# TTGO_shield_revG.net
KiCad netlist of a schematic drawn in EAGLE
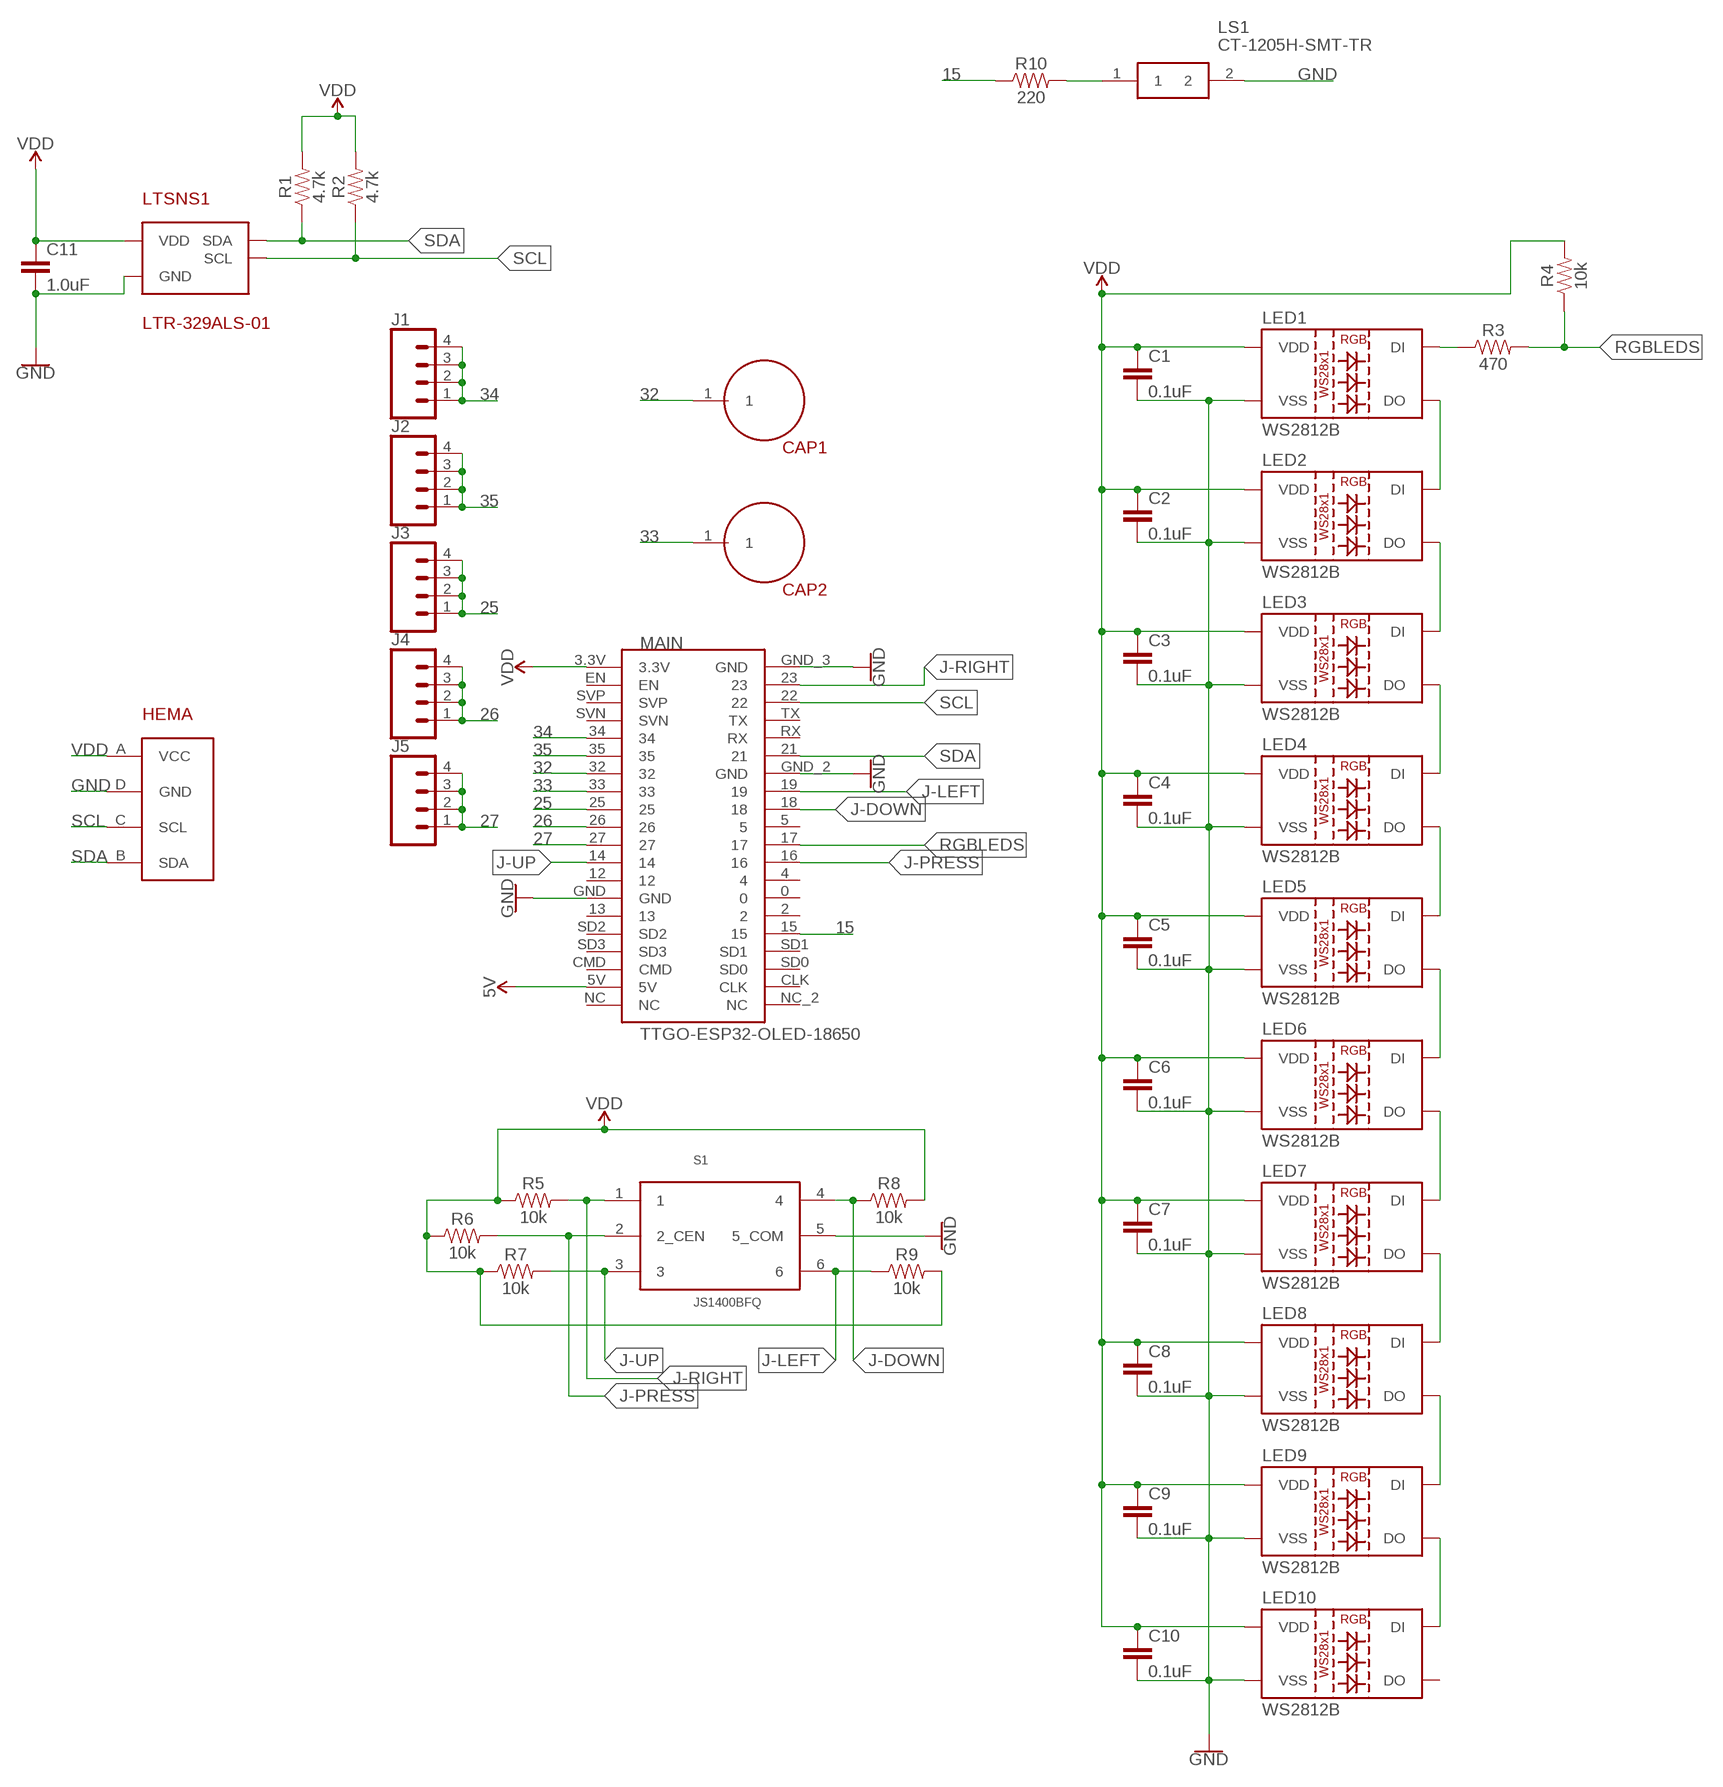
[diagram p0: schematic, sheet 1]

(export (version "E")
  (design (tool "Eeschema 10.0.6"))
  (components
    (comp (ref "C1")
      (value "0.1uF")
      (footprint "eagle-import:0603")
      (libsource (lib "eagle-import") (part "0.1UF-0603-25V-5%"))
    )
    (comp (ref "C2")
      (value "0.1uF")
      (footprint "eagle-import:0603")
      (libsource (lib "eagle-import") (part "0.1UF-0603-25V-5%"))
    )
    (comp (ref "C3")
      (value "0.1uF")
      (footprint "eagle-import:0603")
      (libsource (lib "eagle-import") (part "0.1UF-0603-25V-5%"))
    )
    (comp (ref "C4")
      (value "0.1uF")
      (footprint "eagle-import:0603")
      (libsource (lib "eagle-import") (part "0.1UF-0603-25V-5%"))
    )
    (comp (ref "C5")
      (value "0.1uF")
      (footprint "eagle-import:0603")
      (libsource (lib "eagle-import") (part "0.1UF-0603-25V-5%"))
    )
    (comp (ref "C6")
      (value "0.1uF")
      (footprint "eagle-import:0603")
      (libsource (lib "eagle-import") (part "0.1UF-0603-25V-5%"))
    )
    (comp (ref "C7")
      (value "0.1uF")
      (footprint "eagle-import:0603")
      (libsource (lib "eagle-import") (part "0.1UF-0603-25V-5%"))
    )
    (comp (ref "C8")
      (value "0.1uF")
      (footprint "eagle-import:0603")
      (libsource (lib "eagle-import") (part "0.1UF-0603-25V-5%"))
    )
    (comp (ref "C9")
      (value "0.1uF")
      (footprint "eagle-import:0603")
      (libsource (lib "eagle-import") (part "0.1UF-0603-25V-5%"))
    )
    (comp (ref "C10")
      (value "0.1uF")
      (footprint "eagle-import:0603")
      (libsource (lib "eagle-import") (part "0.1UF-0603-25V-5%"))
    )
    (comp (ref "C11")
      (value "1.0uF")
      (footprint "eagle-import:0805")
      (libsource (lib "eagle-import") (part "1.0UF-0805-25V-10%"))
    )
    (comp (ref "CAP1")
      (value "CAPSENSE_BUTTON")
      (footprint "eagle-import:CAPSENSE_BUTTON")
      (libsource (lib "eagle-import") (part "CAPSENSE_BUTTON"))
    )
    (comp (ref "CAP2")
      (value "CAPSENSE_BUTTON")
      (footprint "eagle-import:CAPSENSE_BUTTON")
      (libsource (lib "eagle-import") (part "CAPSENSE_BUTTON"))
    )
    (comp (ref "J1")
      (value "CONN_04LONGPADS")
      (footprint "eagle-import:1X04_LONGPADS")
      (libsource (lib "eagle-import") (part "CONN_04LONGPADS"))
    )
    (comp (ref "J2")
      (value "CONN_04LONGPADS")
      (footprint "eagle-import:1X04_LONGPADS")
      (libsource (lib "eagle-import") (part "CONN_04LONGPADS"))
    )
    (comp (ref "J3")
      (value "CONN_04LONGPADS")
      (footprint "eagle-import:1X04_LONGPADS")
      (libsource (lib "eagle-import") (part "CONN_04LONGPADS"))
    )
    (comp (ref "J4")
      (value "CONN_04LONGPADS")
      (footprint "eagle-import:1X04_LONGPADS")
      (libsource (lib "eagle-import") (part "CONN_04LONGPADS"))
    )
    (comp (ref "J5")
      (value "CONN_04LONGPADS")
      (footprint "eagle-import:1X04_LONGPADS")
      (libsource (lib "eagle-import") (part "CONN_04LONGPADS"))
    )
    (comp (ref "LED1")
      (value "WS2812B")
      (footprint "eagle-import:WS2812B")
      (libsource (lib "eagle-import") (part "WS2812B"))
    )
    (comp (ref "LED2")
      (value "WS2812B")
      (footprint "eagle-import:WS2812B")
      (libsource (lib "eagle-import") (part "WS2812B"))
    )
    (comp (ref "LED3")
      (value "WS2812B")
      (footprint "eagle-import:WS2812B")
      (libsource (lib "eagle-import") (part "WS2812B"))
    )
    (comp (ref "LED4")
      (value "WS2812B")
      (footprint "eagle-import:WS2812B")
      (libsource (lib "eagle-import") (part "WS2812B"))
    )
    (comp (ref "LED5")
      (value "WS2812B")
      (footprint "eagle-import:WS2812B")
      (libsource (lib "eagle-import") (part "WS2812B"))
    )
    (comp (ref "LED6")
      (value "WS2812B")
      (footprint "eagle-import:WS2812B")
      (libsource (lib "eagle-import") (part "WS2812B"))
    )
    (comp (ref "LED7")
      (value "WS2812B")
      (footprint "eagle-import:WS2812B")
      (libsource (lib "eagle-import") (part "WS2812B"))
    )
    (comp (ref "LED8")
      (value "WS2812B")
      (footprint "eagle-import:WS2812B")
      (libsource (lib "eagle-import") (part "WS2812B"))
    )
    (comp (ref "LED9")
      (value "WS2812B")
      (footprint "eagle-import:WS2812B")
      (libsource (lib "eagle-import") (part "WS2812B"))
    )
    (comp (ref "LED10")
      (value "WS2812B")
      (footprint "eagle-import:WS2812B")
      (libsource (lib "eagle-import") (part "WS2812B"))
    )
    (comp (ref "LS1")
      (value "CT-1205H-SMT-TR")
      (footprint "eagle-import:CT1205HSMTTR")
      (libsource (lib "eagle-import") (part "CT-1205H-SMT-TR"))
    )
    (comp (ref "LTSNS1")
      (value "LTR-329ALS-01")
      (footprint "eagle-import:CHIPLED-4")
      (libsource (lib "eagle-import") (part "LTR-329ALS-01"))
    )
    (comp (ref "MAIN")
      (value "TTGO-ESP32-OLED-18650")
      (footprint "eagle-import:TTGO-ESP32-OLED-18650")
      (libsource (lib "eagle-import") (part "TTGO-ESP32-OLED-18650"))
    )
    (comp (ref "R1")
      (value "4.7k")
      (footprint "eagle-import:0603")
      (libsource (lib "eagle-import") (part "4.7KOHM-0603-1/10W-1%"))
    )
    (comp (ref "R2")
      (value "4.7k")
      (footprint "eagle-import:0603")
      (libsource (lib "eagle-import") (part "4.7KOHM-0603-1/10W-1%"))
    )
    (comp (ref "R3")
      (value "470")
      (footprint "eagle-import:0603")
      (libsource (lib "eagle-import") (part "470OHM-0603-1/10W-1%"))
    )
    (comp (ref "R4")
      (value "10k")
      (footprint "eagle-import:0603")
      (libsource (lib "eagle-import") (part "10KOHM-0603-1/10W-1%"))
    )
    (comp (ref "R5")
      (value "10k")
      (footprint "eagle-import:0603")
      (libsource (lib "eagle-import") (part "10KOHM-0603-1/10W-1%"))
    )
    (comp (ref "R6")
      (value "10k")
      (footprint "eagle-import:0603")
      (libsource (lib "eagle-import") (part "10KOHM-0603-1/10W-1%"))
    )
    (comp (ref "R7")
      (value "10k")
      (footprint "eagle-import:0603")
      (libsource (lib "eagle-import") (part "10KOHM-0603-1/10W-1%"))
    )
    (comp (ref "R8")
      (value "10k")
      (footprint "eagle-import:0603")
      (libsource (lib "eagle-import") (part "10KOHM-0603-1/10W-1%"))
    )
    (comp (ref "R9")
      (value "10k")
      (footprint "eagle-import:0603")
      (libsource (lib "eagle-import") (part "10KOHM-0603-1/10W-1%"))
    )
    (comp (ref "R10")
      (value "220")
      (footprint "eagle-import:0603")
      (libsource (lib "eagle-import") (part "470OHM-0603-1/10W-1%"))
    )
    (comp (ref "S1")
      (value "JS1400BFQ")
      (footprint "eagle-import:JS1400BFQ")
      (libsource (lib "eagle-import") (part "JS1400BFQ"))
    )
    (comp (ref "U$1")
      (value "HEMA-TTGO")
      (footprint "eagle-import:HEMA-TTGO")
      (libsource (lib "eagle-import") (part "HEMA-TTGO"))
    )
  )
  (nets
    (net (code "1") (name "/15") (class "Default")
      (node (ref "MAIN") (pin "15") (pinfunction "15_15") (pintype "bidirectional"))
      (node (ref "R10") (pin "1") (pinfunction "1_1") (pintype "passive"))
    )
    (net (code "2") (name "/25") (class "Default")
      (node (ref "J3") (pin "1") (pinfunction "1_1") (pintype "passive"))
      (node (ref "J3") (pin "2") (pinfunction "2_2") (pintype "passive"))
      (node (ref "J3") (pin "3") (pinfunction "3_3") (pintype "passive"))
      (node (ref "J3") (pin "4") (pinfunction "4_4") (pintype "passive"))
      (node (ref "MAIN") (pin "25") (pinfunction "25_25") (pintype "bidirectional"))
    )
    (net (code "3") (name "/26") (class "Default")
      (node (ref "J4") (pin "1") (pinfunction "1_1") (pintype "passive"))
      (node (ref "J4") (pin "2") (pinfunction "2_2") (pintype "passive"))
      (node (ref "J4") (pin "3") (pinfunction "3_3") (pintype "passive"))
      (node (ref "J4") (pin "4") (pinfunction "4_4") (pintype "passive"))
      (node (ref "MAIN") (pin "26") (pinfunction "26_26") (pintype "bidirectional"))
    )
    (net (code "4") (name "/27") (class "Default")
      (node (ref "J5") (pin "1") (pinfunction "1_1") (pintype "passive"))
      (node (ref "J5") (pin "2") (pinfunction "2_2") (pintype "passive"))
      (node (ref "J5") (pin "3") (pinfunction "3_3") (pintype "passive"))
      (node (ref "J5") (pin "4") (pinfunction "4_4") (pintype "passive"))
      (node (ref "MAIN") (pin "27") (pinfunction "27_27") (pintype "bidirectional"))
    )
    (net (code "5") (name "/32") (class "Default")
      (node (ref "CAP1") (pin "1") (pinfunction "1_1") (pintype "bidirectional"))
      (node (ref "MAIN") (pin "32") (pinfunction "32_32") (pintype "bidirectional"))
    )
    (net (code "6") (name "/33") (class "Default")
      (node (ref "CAP2") (pin "1") (pinfunction "1_1") (pintype "bidirectional"))
      (node (ref "MAIN") (pin "33") (pinfunction "33_33") (pintype "bidirectional"))
    )
    (net (code "7") (name "/34") (class "Default")
      (node (ref "J1") (pin "1") (pinfunction "1_1") (pintype "passive"))
      (node (ref "J1") (pin "2") (pinfunction "2_2") (pintype "passive"))
      (node (ref "J1") (pin "3") (pinfunction "3_3") (pintype "passive"))
      (node (ref "J1") (pin "4") (pinfunction "4_4") (pintype "passive"))
      (node (ref "MAIN") (pin "34") (pinfunction "34_34") (pintype "bidirectional"))
    )
    (net (code "8") (name "/35") (class "Default")
      (node (ref "J2") (pin "1") (pinfunction "1_1") (pintype "passive"))
      (node (ref "J2") (pin "2") (pinfunction "2_2") (pintype "passive"))
      (node (ref "J2") (pin "3") (pinfunction "3_3") (pintype "passive"))
      (node (ref "J2") (pin "4") (pinfunction "4_4") (pintype "passive"))
      (node (ref "MAIN") (pin "35") (pinfunction "35_35") (pintype "bidirectional"))
    )
    (net (code "9") (name "5V") (class "Default")
      (node (ref "MAIN") (pin "5V") (pinfunction "5V_5V") (pintype "bidirectional"))
    )
    (net (code "10") (name "GND") (class "Default")
      (node (ref "C1") (pin "2") (pinfunction "2_2") (pintype "passive"))
      (node (ref "C10") (pin "2") (pinfunction "2_2") (pintype "passive"))
      (node (ref "C11") (pin "2") (pinfunction "2_2") (pintype "passive"))
      (node (ref "C2") (pin "2") (pinfunction "2_2") (pintype "passive"))
      (node (ref "C3") (pin "2") (pinfunction "2_2") (pintype "passive"))
      (node (ref "C4") (pin "2") (pinfunction "2_2") (pintype "passive"))
      (node (ref "C5") (pin "2") (pinfunction "2_2") (pintype "passive"))
      (node (ref "C6") (pin "2") (pinfunction "2_2") (pintype "passive"))
      (node (ref "C7") (pin "2") (pinfunction "2_2") (pintype "passive"))
      (node (ref "C8") (pin "2") (pinfunction "2_2") (pintype "passive"))
      (node (ref "C9") (pin "2") (pinfunction "2_2") (pintype "passive"))
      (node (ref "LED1") (pin "3") (pinfunction "VSS_3") (pintype "bidirectional"))
      (node (ref "LED10") (pin "3") (pinfunction "VSS_3") (pintype "bidirectional"))
      (node (ref "LED2") (pin "3") (pinfunction "VSS_3") (pintype "bidirectional"))
      (node (ref "LED3") (pin "3") (pinfunction "VSS_3") (pintype "bidirectional"))
      (node (ref "LED4") (pin "3") (pinfunction "VSS_3") (pintype "bidirectional"))
      (node (ref "LED5") (pin "3") (pinfunction "VSS_3") (pintype "bidirectional"))
      (node (ref "LED6") (pin "3") (pinfunction "VSS_3") (pintype "bidirectional"))
      (node (ref "LED7") (pin "3") (pinfunction "VSS_3") (pintype "bidirectional"))
      (node (ref "LED8") (pin "3") (pinfunction "VSS_3") (pintype "bidirectional"))
      (node (ref "LED9") (pin "3") (pinfunction "VSS_3") (pintype "bidirectional"))
      (node (ref "LS1") (pin "2") (pinfunction "2_2") (pintype "bidirectional"))
      (node (ref "LTSNS1") (pin "2") (pinfunction "GND_2") (pintype "bidirectional"))
      (node (ref "MAIN") (pin "GND") (pinfunction "GND_GND") (pintype "bidirectional"))
      (node (ref "MAIN") (pin "GND_2") (pinfunction "GND_GND_2") (pintype "bidirectional"))
      (node (ref "MAIN") (pin "GND_3") (pinfunction "GND_GND_3") (pintype "bidirectional"))
      (node (ref "S1") (pin "5") (pinfunction "5_COM_5") (pintype "bidirectional"))
      (node (ref "U$1") (pin "D") (pinfunction "GND_D") (pintype "bidirectional"))
    )
    (net (code "11") (name "J-DOWN") (class "Default")
      (node (ref "MAIN") (pin "18") (pinfunction "18_18") (pintype "bidirectional"))
      (node (ref "R8") (pin "1") (pinfunction "1_1") (pintype "passive"))
      (node (ref "S1") (pin "4") (pinfunction "4_4") (pintype "bidirectional"))
    )
    (net (code "12") (name "J-LEFT") (class "Default")
      (node (ref "MAIN") (pin "19") (pinfunction "19_19") (pintype "bidirectional"))
      (node (ref "R9") (pin "1") (pinfunction "1_1") (pintype "passive"))
      (node (ref "S1") (pin "6") (pinfunction "6_6") (pintype "bidirectional"))
    )
    (net (code "13") (name "J-PRESS") (class "Default")
      (node (ref "MAIN") (pin "16") (pinfunction "16_16") (pintype "bidirectional"))
      (node (ref "R6") (pin "2") (pinfunction "2_2") (pintype "passive"))
      (node (ref "S1") (pin "2") (pinfunction "2_CEN_2") (pintype "bidirectional"))
    )
    (net (code "14") (name "J-RIGHT") (class "Default")
      (node (ref "MAIN") (pin "23") (pinfunction "23_23") (pintype "bidirectional"))
      (node (ref "R5") (pin "2") (pinfunction "2_2") (pintype "passive"))
      (node (ref "S1") (pin "1") (pinfunction "1_1") (pintype "bidirectional"))
    )
    (net (code "15") (name "J-UP") (class "Default")
      (node (ref "MAIN") (pin "14") (pinfunction "14_14") (pintype "bidirectional"))
      (node (ref "R7") (pin "2") (pinfunction "2_2") (pintype "passive"))
      (node (ref "S1") (pin "3") (pinfunction "3_3") (pintype "bidirectional"))
    )
    (net (code "16") (name "Net-(LED1-DI)") (class "Default")
      (node (ref "LED1") (pin "4") (pinfunction "DI_4") (pintype "bidirectional"))
      (node (ref "R3") (pin "1") (pinfunction "1_1") (pintype "passive"))
    )
    (net (code "17") (name "Net-(LED1-DO)") (class "Default")
      (node (ref "LED1") (pin "2") (pinfunction "DO_2") (pintype "bidirectional"))
      (node (ref "LED2") (pin "4") (pinfunction "DI_4") (pintype "bidirectional"))
    )
    (net (code "18") (name "Net-(LED2-DO)") (class "Default")
      (node (ref "LED2") (pin "2") (pinfunction "DO_2") (pintype "bidirectional"))
      (node (ref "LED3") (pin "4") (pinfunction "DI_4") (pintype "bidirectional"))
    )
    (net (code "19") (name "Net-(LED3-DO)") (class "Default")
      (node (ref "LED3") (pin "2") (pinfunction "DO_2") (pintype "bidirectional"))
      (node (ref "LED4") (pin "4") (pinfunction "DI_4") (pintype "bidirectional"))
    )
    (net (code "20") (name "Net-(LED4-DO)") (class "Default")
      (node (ref "LED4") (pin "2") (pinfunction "DO_2") (pintype "bidirectional"))
      (node (ref "LED5") (pin "4") (pinfunction "DI_4") (pintype "bidirectional"))
    )
    (net (code "21") (name "Net-(LED5-DO)") (class "Default")
      (node (ref "LED5") (pin "2") (pinfunction "DO_2") (pintype "bidirectional"))
      (node (ref "LED6") (pin "4") (pinfunction "DI_4") (pintype "bidirectional"))
    )
    (net (code "22") (name "Net-(LED6-DO)") (class "Default")
      (node (ref "LED6") (pin "2") (pinfunction "DO_2") (pintype "bidirectional"))
      (node (ref "LED7") (pin "4") (pinfunction "DI_4") (pintype "bidirectional"))
    )
    (net (code "23") (name "Net-(LED7-DO)") (class "Default")
      (node (ref "LED7") (pin "2") (pinfunction "DO_2") (pintype "bidirectional"))
      (node (ref "LED8") (pin "4") (pinfunction "DI_4") (pintype "bidirectional"))
    )
    (net (code "24") (name "Net-(LED8-DO)") (class "Default")
      (node (ref "LED8") (pin "2") (pinfunction "DO_2") (pintype "bidirectional"))
      (node (ref "LED9") (pin "4") (pinfunction "DI_4") (pintype "bidirectional"))
    )
    (net (code "25") (name "Net-(LED10-DI)") (class "Default")
      (node (ref "LED10") (pin "4") (pinfunction "DI_4") (pintype "bidirectional"))
      (node (ref "LED9") (pin "2") (pinfunction "DO_2") (pintype "bidirectional"))
    )
    (net (code "26") (name "Net-(LS1-Pad1)") (class "Default")
      (node (ref "LS1") (pin "1") (pinfunction "1_1") (pintype "bidirectional"))
      (node (ref "R10") (pin "2") (pinfunction "2_2") (pintype "passive"))
    )
    (net (code "27") (name "RGBLEDS") (class "Default")
      (node (ref "MAIN") (pin "17") (pinfunction "17_17") (pintype "bidirectional"))
      (node (ref "R3") (pin "2") (pinfunction "2_2") (pintype "passive"))
      (node (ref "R4") (pin "1") (pinfunction "1_1") (pintype "passive"))
    )
    (net (code "28") (name "SCL") (class "Default")
      (node (ref "LTSNS1") (pin "4") (pinfunction "SCL_4") (pintype "bidirectional"))
      (node (ref "MAIN") (pin "22") (pinfunction "22_22") (pintype "bidirectional"))
      (node (ref "R2") (pin "1") (pinfunction "1_1") (pintype "passive"))
      (node (ref "U$1") (pin "C") (pinfunction "SCL_C") (pintype "bidirectional"))
    )
    (net (code "29") (name "SDA") (class "Default")
      (node (ref "LTSNS1") (pin "3") (pinfunction "SDA_3") (pintype "bidirectional"))
      (node (ref "MAIN") (pin "21") (pinfunction "21_21") (pintype "bidirectional"))
      (node (ref "R1") (pin "1") (pinfunction "1_1") (pintype "passive"))
      (node (ref "U$1") (pin "B") (pinfunction "SDA_B") (pintype "bidirectional"))
    )
    (net (code "30") (name "VDD") (class "Default")
      (node (ref "C1") (pin "1") (pinfunction "1_1") (pintype "passive"))
      (node (ref "C10") (pin "1") (pinfunction "1_1") (pintype "passive"))
      (node (ref "C11") (pin "1") (pinfunction "1_1") (pintype "passive"))
      (node (ref "C2") (pin "1") (pinfunction "1_1") (pintype "passive"))
      (node (ref "C3") (pin "1") (pinfunction "1_1") (pintype "passive"))
      (node (ref "C4") (pin "1") (pinfunction "1_1") (pintype "passive"))
      (node (ref "C5") (pin "1") (pinfunction "1_1") (pintype "passive"))
      (node (ref "C6") (pin "1") (pinfunction "1_1") (pintype "passive"))
      (node (ref "C7") (pin "1") (pinfunction "1_1") (pintype "passive"))
      (node (ref "C8") (pin "1") (pinfunction "1_1") (pintype "passive"))
      (node (ref "C9") (pin "1") (pinfunction "1_1") (pintype "passive"))
      (node (ref "LED1") (pin "1") (pinfunction "VDD_1") (pintype "bidirectional"))
      (node (ref "LED10") (pin "1") (pinfunction "VDD_1") (pintype "bidirectional"))
      (node (ref "LED2") (pin "1") (pinfunction "VDD_1") (pintype "bidirectional"))
      (node (ref "LED3") (pin "1") (pinfunction "VDD_1") (pintype "bidirectional"))
      (node (ref "LED4") (pin "1") (pinfunction "VDD_1") (pintype "bidirectional"))
      (node (ref "LED5") (pin "1") (pinfunction "VDD_1") (pintype "bidirectional"))
      (node (ref "LED6") (pin "1") (pinfunction "VDD_1") (pintype "bidirectional"))
      (node (ref "LED7") (pin "1") (pinfunction "VDD_1") (pintype "bidirectional"))
      (node (ref "LED8") (pin "1") (pinfunction "VDD_1") (pintype "bidirectional"))
      (node (ref "LED9") (pin "1") (pinfunction "VDD_1") (pintype "bidirectional"))
      (node (ref "LTSNS1") (pin "1") (pinfunction "VDD_1") (pintype "bidirectional"))
      (node (ref "MAIN") (pin "3.3V") (pinfunction "3.3V_3.3V") (pintype "bidirectional"))
      (node (ref "R1") (pin "2") (pinfunction "2_2") (pintype "passive"))
      (node (ref "R2") (pin "2") (pinfunction "2_2") (pintype "passive"))
      (node (ref "R4") (pin "2") (pinfunction "2_2") (pintype "passive"))
      (node (ref "R5") (pin "1") (pinfunction "1_1") (pintype "passive"))
      (node (ref "R6") (pin "1") (pinfunction "1_1") (pintype "passive"))
      (node (ref "R7") (pin "1") (pinfunction "1_1") (pintype "passive"))
      (node (ref "R8") (pin "2") (pinfunction "2_2") (pintype "passive"))
      (node (ref "R9") (pin "2") (pinfunction "2_2") (pintype "passive"))
      (node (ref "U$1") (pin "A") (pinfunction "VCC_A") (pintype "bidirectional"))
    )
    (net (code "31") (name "unconnected-(LED10-DO-Pad2)") (class "Default")
      (node (ref "LED10") (pin "2") (pinfunction "DO_2") (pintype "bidirectional"))
    )
    (net (code "32") (name "unconnected-(MAIN-NC-PadNC_2)") (class "Default")
      (node (ref "MAIN") (pin "NC_2") (pinfunction "NC_NC_2") (pintype "bidirectional"))
    )
    (net (code "33") (name "unconnected-(MAIN-Pad0)") (class "Default")
      (node (ref "MAIN") (pin "0") (pinfunction "0_0") (pintype "bidirectional"))
    )
    (net (code "34") (name "unconnected-(MAIN-Pad2)") (class "Default")
      (node (ref "MAIN") (pin "2") (pinfunction "2_2") (pintype "bidirectional"))
    )
    (net (code "35") (name "unconnected-(MAIN-Pad4)") (class "Default")
      (node (ref "MAIN") (pin "4") (pinfunction "4_4") (pintype "bidirectional"))
    )
    (net (code "36") (name "unconnected-(MAIN-Pad5)") (class "Default")
      (node (ref "MAIN") (pin "5") (pinfunction "5_5") (pintype "bidirectional"))
    )
    (net (code "37") (name "unconnected-(MAIN-Pad12)") (class "Default")
      (node (ref "MAIN") (pin "12") (pinfunction "12_12") (pintype "bidirectional"))
    )
    (net (code "38") (name "unconnected-(MAIN-Pad13)") (class "Default")
      (node (ref "MAIN") (pin "13") (pinfunction "13_13") (pintype "bidirectional"))
    )
    (net (code "39") (name "unconnected-(MAIN-PadCLK)") (class "Default")
      (node (ref "MAIN") (pin "CLK") (pinfunction "CLK_CLK") (pintype "bidirectional"))
    )
    (net (code "40") (name "unconnected-(MAIN-PadCMD)") (class "Default")
      (node (ref "MAIN") (pin "CMD") (pinfunction "CMD_CMD") (pintype "bidirectional"))
    )
    (net (code "41") (name "unconnected-(MAIN-PadEN)") (class "Default")
      (node (ref "MAIN") (pin "EN") (pinfunction "EN_EN") (pintype "bidirectional"))
    )
    (net (code "42") (name "unconnected-(MAIN-PadNC)") (class "Default")
      (node (ref "MAIN") (pin "NC") (pinfunction "NC_NC") (pintype "bidirectional"))
    )
    (net (code "43") (name "unconnected-(MAIN-PadRX)") (class "Default")
      (node (ref "MAIN") (pin "RX") (pinfunction "RX_RX") (pintype "bidirectional"))
    )
    (net (code "44") (name "unconnected-(MAIN-PadSD0)") (class "Default")
      (node (ref "MAIN") (pin "SD0") (pinfunction "SD0_SD0") (pintype "bidirectional"))
    )
    (net (code "45") (name "unconnected-(MAIN-PadSD1)") (class "Default")
      (node (ref "MAIN") (pin "SD1") (pinfunction "SD1_SD1") (pintype "bidirectional"))
    )
    (net (code "46") (name "unconnected-(MAIN-PadSD2)") (class "Default")
      (node (ref "MAIN") (pin "SD2") (pinfunction "SD2_SD2") (pintype "bidirectional"))
    )
    (net (code "47") (name "unconnected-(MAIN-PadSD3)") (class "Default")
      (node (ref "MAIN") (pin "SD3") (pinfunction "SD3_SD3") (pintype "bidirectional"))
    )
    (net (code "48") (name "unconnected-(MAIN-PadSVN)") (class "Default")
      (node (ref "MAIN") (pin "SVN") (pinfunction "SVN_SVN") (pintype "bidirectional"))
    )
    (net (code "49") (name "unconnected-(MAIN-PadSVP)") (class "Default")
      (node (ref "MAIN") (pin "SVP") (pinfunction "SVP_SVP") (pintype "bidirectional"))
    )
    (net (code "50") (name "unconnected-(MAIN-PadTX)") (class "Default")
      (node (ref "MAIN") (pin "TX") (pinfunction "TX_TX") (pintype "bidirectional"))
    )
  )
)
